# 004.net
KiCad netlist of a schematic drawn in EAGLE
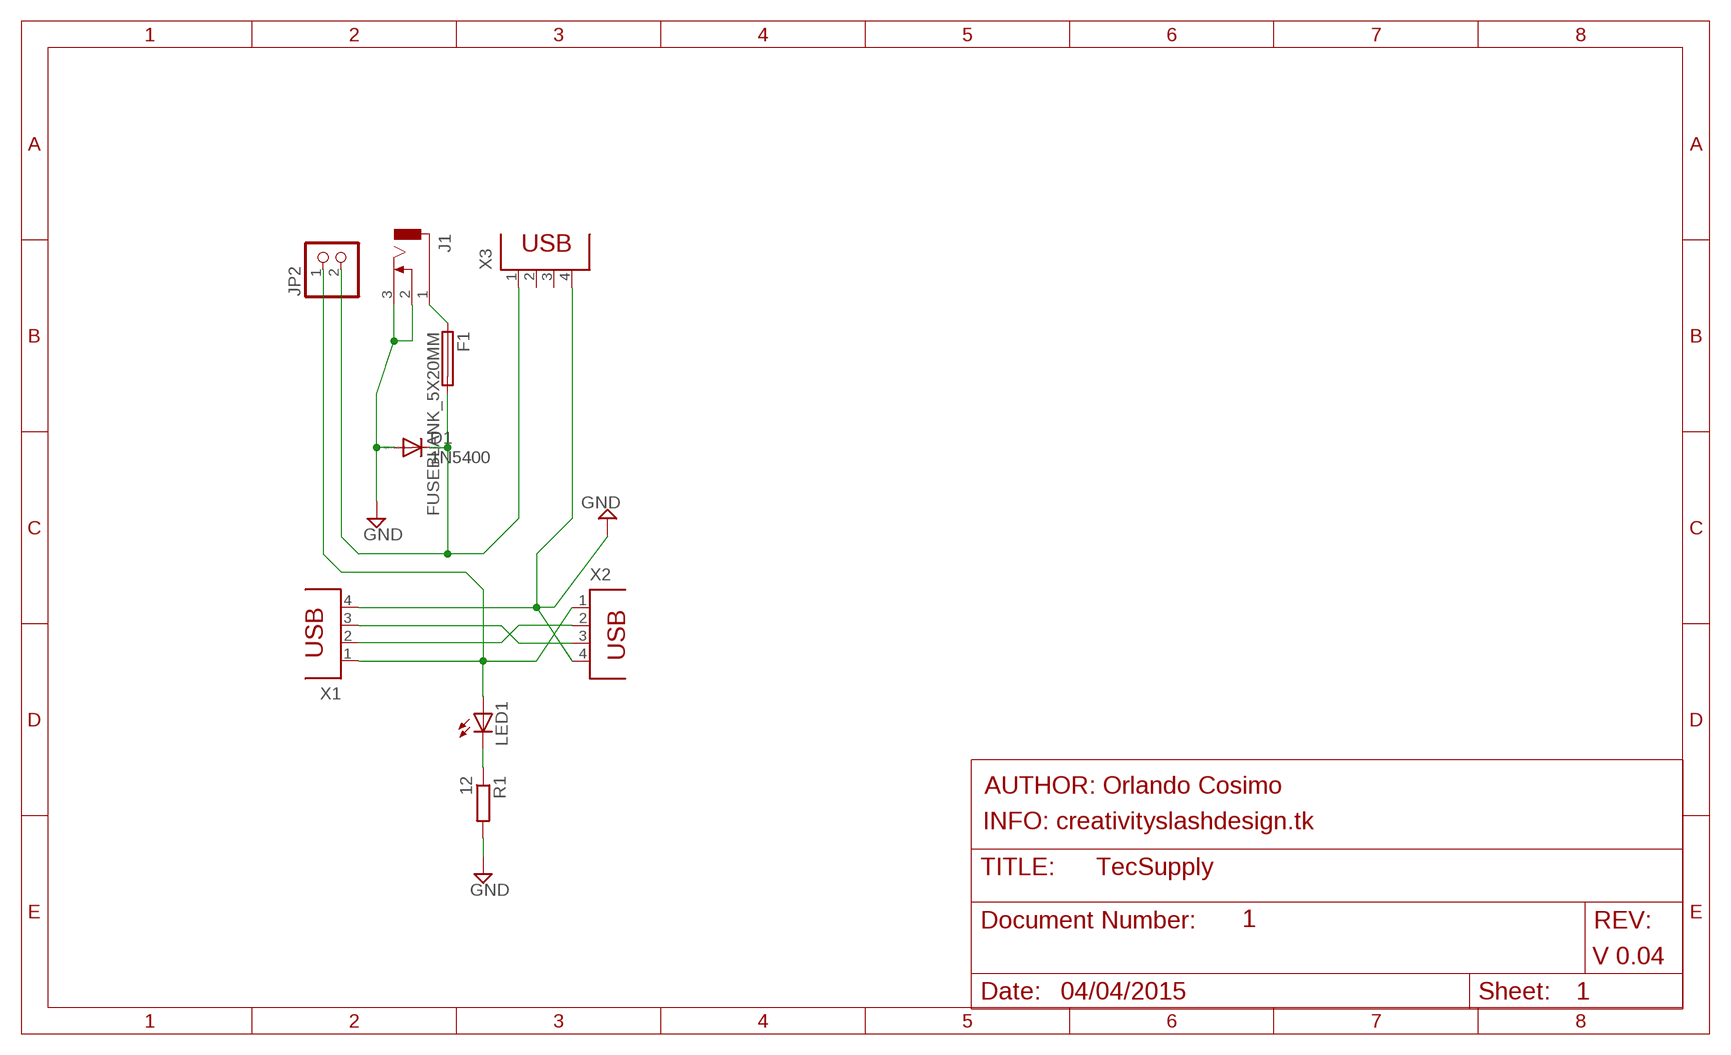
[diagram p0: schematic, sheet 1]

(export (version "E")
  (design (tool "Eeschema 10.0.6"))
  (components
    (comp (ref "D1")
      (value "1N5400")
      (footprint "eagle-import:DO201-15")
      (libsource (lib "eagle-import") (part "1N5400"))
    )
    (comp (ref "F1")
      (value "FUSEBLANK_5X20MM")
      (footprint "eagle-import:FUSE_HOLDER_5X20MM")
      (libsource (lib "eagle-import") (part "FUSEBLANK_5X20MM"))
    )
    (comp (ref "J1")
      (value "DCJ0303")
      (footprint "eagle-import:DCJ0303")
      (libsource (lib "eagle-import") (part "DCJ0303"))
    )
    (comp (ref "JP2")
      (value "PINHD-1X2/90")
      (footprint "eagle-import:1X02_90")
      (libsource (lib "eagle-import") (part "PINHD-1X2/90"))
    )
    (comp (ref "LED1")
      (value "LED5MM")
      (footprint "eagle-import:LED5MM")
      (libsource (lib "eagle-import") (part "LED5MM"))
    )
    (comp (ref "R1")
      (value "12")
      (footprint "eagle-import:0204_7")
      (libsource (lib "eagle-import") (part "R-EU_0204/7"))
    )
    (comp (ref "X1")
      (value "PN87520")
      (footprint "eagle-import:PN87520")
      (libsource (lib "eagle-import") (part "PN87520"))
    )
    (comp (ref "X2")
      (value "PN87520")
      (footprint "eagle-import:PN87520")
      (libsource (lib "eagle-import") (part "PN87520"))
    )
    (comp (ref "X3")
      (value "PN87520")
      (footprint "eagle-import:PN87520")
      (libsource (lib "eagle-import") (part "PN87520"))
    )
  )
  (nets
    (net (code "1") (name "GND") (class "Default")
      (node (ref "D1") (pin "A") (pinfunction "A_A") (pintype "passive"))
      (node (ref "J1") (pin "2") (pinfunction "2_2") (pintype "passive"))
      (node (ref "J1") (pin "3") (pinfunction "3_3") (pintype "passive"))
      (node (ref "R1") (pin "2") (pinfunction "2_2") (pintype "passive"))
      (node (ref "X1") (pin "4") (pinfunction "4_4") (pintype "passive"))
      (node (ref "X2") (pin "4") (pinfunction "4_4") (pintype "passive"))
      (node (ref "X3") (pin "4") (pinfunction "4_4") (pintype "passive"))
    )
    (net (code "2") (name "Net-(D1-PadC)") (class "Default")
      (node (ref "D1") (pin "C") (pinfunction "C_C") (pintype "passive"))
      (node (ref "F1") (pin "2") (pinfunction "2_2") (pintype "passive"))
      (node (ref "JP2") (pin "2") (pinfunction "2_2") (pintype "passive"))
      (node (ref "X3") (pin "1") (pinfunction "1_1") (pintype "passive"))
    )
    (net (code "3") (name "Net-(F1-Pad1)") (class "Default")
      (node (ref "F1") (pin "1") (pinfunction "1_1") (pintype "passive"))
      (node (ref "J1") (pin "1") (pinfunction "1_1") (pintype "passive"))
    )
    (net (code "4") (name "Net-(JP2-Pad1)") (class "Default")
      (node (ref "JP2") (pin "1") (pinfunction "1_1") (pintype "passive"))
      (node (ref "LED1") (pin "A") (pinfunction "A_A") (pintype "passive"))
      (node (ref "X1") (pin "1") (pinfunction "1_1") (pintype "passive"))
      (node (ref "X2") (pin "1") (pinfunction "1_1") (pintype "passive"))
    )
    (net (code "5") (name "Net-(LED1-C)") (class "Default")
      (node (ref "LED1") (pin "K") (pinfunction "C_K") (pintype "passive"))
      (node (ref "R1") (pin "1") (pinfunction "1_1") (pintype "passive"))
    )
    (net (code "6") (name "Net-(X1-Pad2)") (class "Default")
      (node (ref "X1") (pin "2") (pinfunction "2_2") (pintype "passive"))
      (node (ref "X2") (pin "2") (pinfunction "2_2") (pintype "passive"))
    )
    (net (code "7") (name "Net-(X1-Pad3)") (class "Default")
      (node (ref "X1") (pin "3") (pinfunction "3_3") (pintype "passive"))
      (node (ref "X2") (pin "3") (pinfunction "3_3") (pintype "passive"))
    )
    (net (code "8") (name "unconnected-(X3-Pad2)") (class "Default")
      (node (ref "X3") (pin "2") (pinfunction "2_2") (pintype "passive"))
    )
    (net (code "9") (name "unconnected-(X3-Pad3)") (class "Default")
      (node (ref "X3") (pin "3") (pinfunction "3_3") (pintype "passive"))
    )
  )
)
